# Flow_Pump.net
KiCad netlist of a schematic drawn in Altium Designer
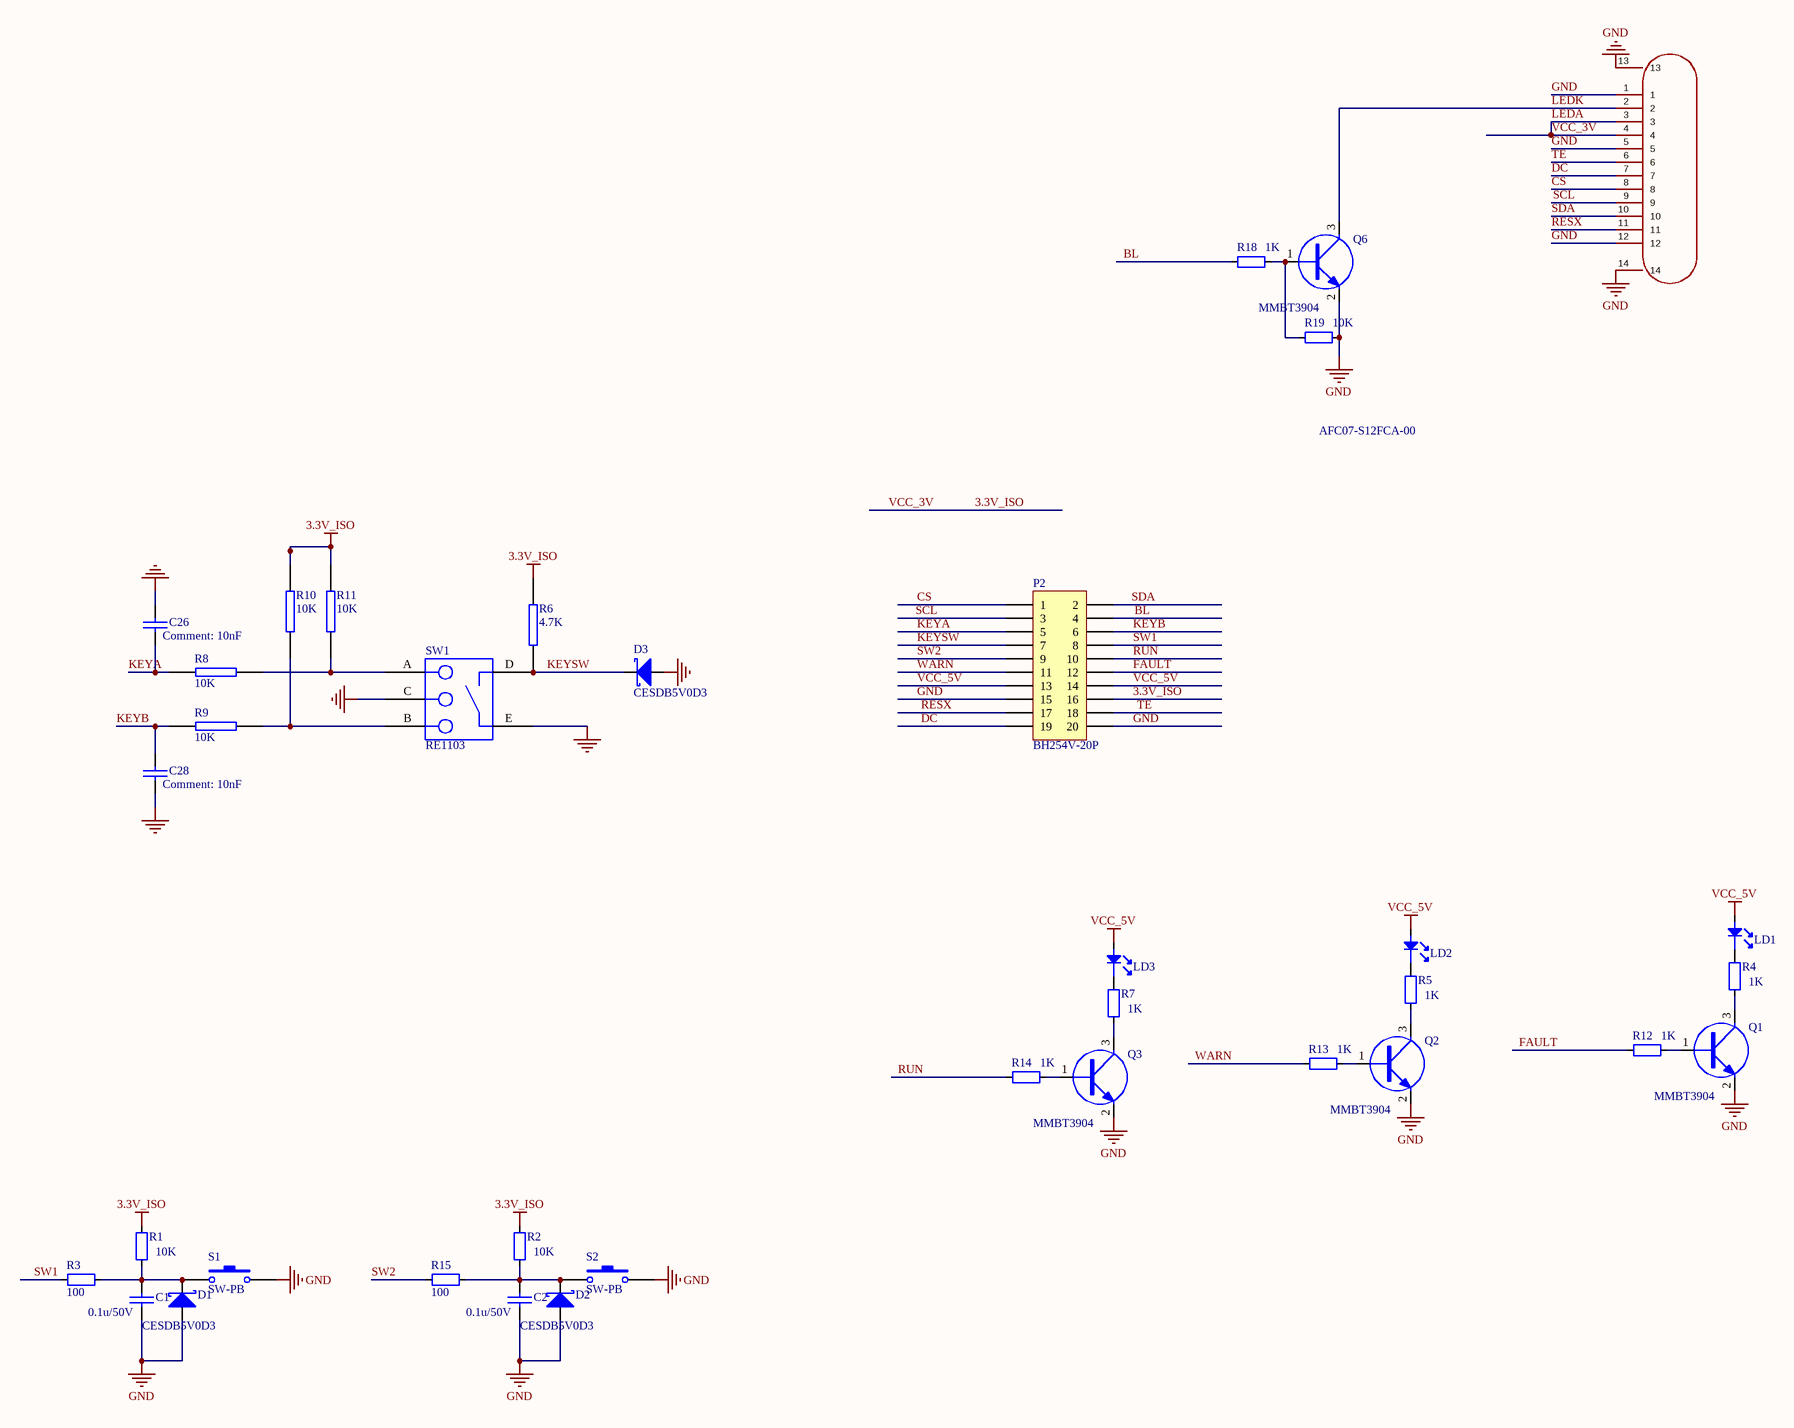
[diagram p0: Flow_Pump显示板.SchDoc]

(export (version "E")
  (design (tool "Eeschema 10.0.6"))
  (components
    (comp (ref "C1")
      (value "0.1u/50V")
      (footprint "0603C")
      (fields (field (name "Comment") "1uF/25V"))
      (libsource (lib "SM") (part "CAP"))
    )
    (comp (ref "C2")
      (value "0.1u/50V")
      (footprint "0603C")
      (fields (field (name "Comment") "1uF/25V"))
      (libsource (lib "SM") (part "CAP"))
    )
    (comp (ref "C26")
      (value "10nF")
      (footprint "0603C")
      (description "Capacitor")
      (libsource (lib "*") (part "CAP"))
    )
    (comp (ref "C28")
      (value "10nF")
      (footprint "0603C")
      (description "Capacitor")
      (libsource (lib "*") (part "CAP"))
    )
    (comp (ref "D1") (value "CESDB5V0D3") (footprint "SOD323") (libsource (lib "*") (part "DIODE S")))
    (comp (ref "D2") (value "CESDB5V0D3") (footprint "SOD323") (libsource (lib "*") (part "DIODE S")))
    (comp (ref "D3") (value "CESDB5V0D3") (footprint "SOD323") (libsource (lib "*") (part "DIODE S")))
    (comp (ref "FPC1")
      (value "AFC07-S12FCA-00")
      (footprint "FPC-SMD_12P-P0.50_AFC07-S12FCA-00")
      (libsource (lib "altium-import") (part "root_0_AFC07-S12FCA-00_"))
    )
    (comp (ref "LD1")
      (value "LED_Green_19-217")
      (footprint "0603led")
      (libsource (lib "RC_M_D_00") (part "LED_Green_19-217"))
    )
    (comp (ref "LD2")
      (value "LED_Green_19-217")
      (footprint "0603led")
      (libsource (lib "RC_M_D_00") (part "LED_Green_19-217"))
    )
    (comp (ref "LD3")
      (value "LED_Green_19-217")
      (footprint "0603led")
      (libsource (lib "RC_M_D_00") (part "LED_Green_19-217"))
    )
    (comp (ref "P2")
      (value "BH254V-20P")
      (footprint "DC-2.54-L-Z-20P")
      (description "Header, 10-Pin, Dual row")
      (fields (field (name "PUBLISHER") "Altium Limited"))
      (libsource (lib "Miscellaneous Connectors") (part "Header 10X2"))
    )
    (comp (ref "Q1")
      (value "MMBT3904")
      (footprint "SOT23-3")
      (libsource (lib "CenLib") (part "NPN_MMBT3904"))
    )
    (comp (ref "Q2")
      (value "MMBT3904")
      (footprint "SOT23-3")
      (libsource (lib "CenLib") (part "NPN_MMBT3904"))
    )
    (comp (ref "Q3")
      (value "MMBT3904")
      (footprint "SOT23-3")
      (libsource (lib "CenLib") (part "NPN_MMBT3904"))
    )
    (comp (ref "Q6")
      (value "MMBT3904")
      (footprint "SOT23-3")
      (libsource (lib "CenLib") (part "NPN_MMBT3904"))
    )
    (comp (ref "R1") (value "10K") (footprint "0603r") (libsource (lib "RC_M_D_00") (part "RES0603")))
    (comp (ref "R2") (value "10K") (footprint "0603r") (libsource (lib "RC_M_D_00") (part "RES0603")))
    (comp (ref "R3") (value "100") (footprint "0603r") (libsource (lib "RC_M_D_00") (part "RES0603")))
    (comp (ref "R4") (value "1K") (footprint "0603r") (libsource (lib "RC_M_D_00") (part "RES0603")))
    (comp (ref "R5") (value "1K") (footprint "0603r") (libsource (lib "RC_M_D_00") (part "RES0603")))
    (comp (ref "R6") (value "4.7K") (footprint "0603R") (libsource (lib "*") (part "RES2")))
    (comp (ref "R7") (value "1K") (footprint "0603r") (libsource (lib "RC_M_D_00") (part "RES0603")))
    (comp (ref "R8") (value "10K") (footprint "0603R") (libsource (lib "*") (part "RES2")))
    (comp (ref "R9") (value "10K") (footprint "0603R") (libsource (lib "*") (part "RES2")))
    (comp (ref "R10") (value "10K") (footprint "0603R") (libsource (lib "*") (part "RES2")))
    (comp (ref "R11") (value "10K") (footprint "0603R") (libsource (lib "*") (part "RES2")))
    (comp (ref "R12") (value "1K") (footprint "0603r") (libsource (lib "RC_M_D_00") (part "RES0603")))
    (comp (ref "R13") (value "1K") (footprint "0603r") (libsource (lib "RC_M_D_00") (part "RES0603")))
    (comp (ref "R14") (value "1K") (footprint "0603r") (libsource (lib "RC_M_D_00") (part "RES0603")))
    (comp (ref "R15") (value "100") (footprint "0603r") (libsource (lib "RC_M_D_00") (part "RES0603")))
    (comp (ref "R18") (value "1K") (footprint "0603r") (libsource (lib "RC_M_D_00") (part "RES0603")))
    (comp (ref "R19") (value "10K") (footprint "0603r") (libsource (lib "RC_M_D_00") (part "RES0603")))
    (comp (ref "S1")
      (value "SW-PB")
      (footprint "TSW SMD-6*6*8")
      (description "Switch")
      (fields (field (name "PUBLISHER") "Altium Limited"))
      (libsource (lib "Miscellaneous Devices") (part "SW-PB"))
    )
    (comp (ref "S2")
      (value "SW-PB")
      (footprint "TSW SMD-6*6*8")
      (description "Switch")
      (fields (field (name "PUBLISHER") "Altium Limited"))
      (libsource (lib "Miscellaneous Devices") (part "SW-PB"))
    )
    (comp (ref "SW1") (value "RE1103") (footprint "EX1103S-D2-10") (libsource (lib "*") (part "RE1103")))
  )
  (nets
    (net (code "1") (name "/BL") (class "Default")
      (node (ref "P2") (pin "4") (pinfunction "4_4") (pintype "passive"))
      (node (ref "R18") (pin "1") (pinfunction "1_1") (pintype "passive"))
    )
    (net (code "2") (name "/CS") (class "Default")
      (node (ref "FPC1") (pin "8") (pinfunction "8_8") (pintype "passive"))
      (node (ref "P2") (pin "1") (pinfunction "1_1") (pintype "passive"))
    )
    (net (code "3") (name "/DC") (class "Default")
      (node (ref "FPC1") (pin "7") (pinfunction "7_7") (pintype "passive"))
      (node (ref "P2") (pin "19") (pinfunction "19_19") (pintype "passive"))
    )
    (net (code "4") (name "/FAULT") (class "Default")
      (node (ref "P2") (pin "12") (pinfunction "12_12") (pintype "passive"))
      (node (ref "R12") (pin "1") (pinfunction "1_1") (pintype "passive"))
    )
    (net (code "5") (name "/KEYA") (class "Default")
      (node (ref "C26") (pin "2") (pinfunction "2_2") (pintype "passive"))
      (node (ref "P2") (pin "5") (pinfunction "5_5") (pintype "passive"))
      (node (ref "R8") (pin "1") (pinfunction "1_1") (pintype "passive"))
    )
    (net (code "6") (name "/KEYB") (class "Default")
      (node (ref "C28") (pin "1") (pinfunction "1_1") (pintype "passive"))
      (node (ref "P2") (pin "6") (pinfunction "6_6") (pintype "passive"))
      (node (ref "R9") (pin "1") (pinfunction "1_1") (pintype "passive"))
    )
    (net (code "7") (name "/KEYSW") (class "Default")
      (node (ref "D3") (pin "2") (pinfunction "K_2") (pintype "passive"))
      (node (ref "P2") (pin "7") (pinfunction "7_7") (pintype "passive"))
      (node (ref "R6") (pin "2") (pinfunction "2_2") (pintype "passive"))
      (node (ref "SW1") (pin "D") (pintype "passive"))
    )
    (net (code "8") (name "/LEDK") (class "Default")
      (node (ref "FPC1") (pin "2") (pinfunction "2_2") (pintype "passive"))
      (node (ref "Q6") (pin "3") (pinfunction "C_3") (pintype "passive"))
    )
    (net (code "9") (name "/RESX") (class "Default")
      (node (ref "FPC1") (pin "11") (pinfunction "11_11") (pintype "passive"))
      (node (ref "P2") (pin "17") (pinfunction "17_17") (pintype "passive"))
    )
    (net (code "10") (name "/RUN") (class "Default")
      (node (ref "P2") (pin "10") (pinfunction "10_10") (pintype "passive"))
      (node (ref "R14") (pin "1") (pinfunction "1_1") (pintype "passive"))
    )
    (net (code "11") (name "/SCL") (class "Default")
      (node (ref "FPC1") (pin "9") (pinfunction "9_9") (pintype "passive"))
      (node (ref "P2") (pin "3") (pinfunction "3_3") (pintype "passive"))
    )
    (net (code "12") (name "/SDA") (class "Default")
      (node (ref "FPC1") (pin "10") (pinfunction "10_10") (pintype "passive"))
      (node (ref "P2") (pin "2") (pinfunction "2_2") (pintype "passive"))
    )
    (net (code "13") (name "/SW1") (class "Default")
      (node (ref "P2") (pin "8") (pinfunction "8_8") (pintype "passive"))
      (node (ref "R3") (pin "1") (pinfunction "1_1") (pintype "passive"))
    )
    (net (code "14") (name "/SW2") (class "Default")
      (node (ref "P2") (pin "9") (pinfunction "9_9") (pintype "passive"))
      (node (ref "R15") (pin "1") (pinfunction "1_1") (pintype "passive"))
    )
    (net (code "15") (name "/TE") (class "Default")
      (node (ref "FPC1") (pin "6") (pinfunction "6_6") (pintype "passive"))
      (node (ref "P2") (pin "18") (pinfunction "18_18") (pintype "passive"))
    )
    (net (code "16") (name "/WARN") (class "Default")
      (node (ref "P2") (pin "11") (pinfunction "11_11") (pintype "passive"))
      (node (ref "R13") (pin "1") (pinfunction "1_1") (pintype "passive"))
    )
    (net (code "17") (name "3.3V_ISO") (class "Default")
      (node (ref "FPC1") (pin "3") (pinfunction "3_3") (pintype "passive"))
      (node (ref "FPC1") (pin "4") (pinfunction "4_4") (pintype "passive"))
      (node (ref "P2") (pin "16") (pinfunction "16_16") (pintype "passive"))
      (node (ref "R1") (pin "1") (pinfunction "1_1") (pintype "passive"))
      (node (ref "R10") (pin "2") (pinfunction "2_2") (pintype "passive"))
      (node (ref "R11") (pin "2") (pinfunction "2_2") (pintype "passive"))
      (node (ref "R2") (pin "1") (pinfunction "1_1") (pintype "passive"))
      (node (ref "R6") (pin "1") (pinfunction "1_1") (pintype "passive"))
    )
    (net (code "18") (name "GND") (class "Default")
      (node (ref "C1") (pin "1") (pinfunction "1_1") (pintype "passive"))
      (node (ref "C2") (pin "1") (pinfunction "1_1") (pintype "passive"))
      (node (ref "C26") (pin "1") (pinfunction "1_1") (pintype "passive"))
      (node (ref "C28") (pin "2") (pinfunction "2_2") (pintype "passive"))
      (node (ref "D1") (pin "1") (pinfunction "A_1") (pintype "passive"))
      (node (ref "D2") (pin "1") (pinfunction "A_1") (pintype "passive"))
      (node (ref "D3") (pin "1") (pinfunction "A_1") (pintype "passive"))
      (node (ref "FPC1") (pin "1") (pinfunction "1_1") (pintype "passive"))
      (node (ref "FPC1") (pin "12") (pinfunction "12_12") (pintype "passive"))
      (node (ref "FPC1") (pin "13") (pinfunction "13_13") (pintype "passive"))
      (node (ref "FPC1") (pin "14") (pinfunction "14_14") (pintype "passive"))
      (node (ref "FPC1") (pin "5") (pinfunction "5_5") (pintype "passive"))
      (node (ref "P2") (pin "15") (pinfunction "15_15") (pintype "passive"))
      (node (ref "P2") (pin "20") (pinfunction "20_20") (pintype "passive"))
      (node (ref "Q1") (pin "2") (pinfunction "E_2") (pintype "passive"))
      (node (ref "Q2") (pin "2") (pinfunction "E_2") (pintype "passive"))
      (node (ref "Q3") (pin "2") (pinfunction "E_2") (pintype "passive"))
      (node (ref "Q6") (pin "2") (pinfunction "E_2") (pintype "passive"))
      (node (ref "R19") (pin "2") (pinfunction "2_2") (pintype "passive"))
      (node (ref "S1") (pin "2") (pinfunction "2_2") (pintype "passive"))
      (node (ref "S2") (pin "2") (pinfunction "2_2") (pintype "passive"))
      (node (ref "SW1") (pin "C") (pintype "passive"))
      (node (ref "SW1") (pin "E") (pintype "passive"))
    )
    (net (code "19") (name "Net-(D1-K)") (class "Default")
      (node (ref "C1") (pin "2") (pinfunction "2_2") (pintype "passive"))
      (node (ref "D1") (pin "2") (pinfunction "K_2") (pintype "passive"))
      (node (ref "R1") (pin "2") (pinfunction "2_2") (pintype "passive"))
      (node (ref "R3") (pin "2") (pinfunction "2_2") (pintype "passive"))
      (node (ref "S1") (pin "1") (pinfunction "1_1") (pintype "passive"))
    )
    (net (code "20") (name "Net-(D2-K)") (class "Default")
      (node (ref "C2") (pin "2") (pinfunction "2_2") (pintype "passive"))
      (node (ref "D2") (pin "2") (pinfunction "K_2") (pintype "passive"))
      (node (ref "R15") (pin "2") (pinfunction "2_2") (pintype "passive"))
      (node (ref "R2") (pin "2") (pinfunction "2_2") (pintype "passive"))
      (node (ref "S2") (pin "1") (pinfunction "1_1") (pintype "passive"))
    )
    (net (code "21") (name "Net-(LD1-Pad2)") (class "Default")
      (node (ref "LD1") (pin "2") (pinfunction "2_2") (pintype "passive"))
      (node (ref "R4") (pin "1") (pinfunction "1_1") (pintype "passive"))
    )
    (net (code "22") (name "Net-(LD2-Pad2)") (class "Default")
      (node (ref "LD2") (pin "2") (pinfunction "2_2") (pintype "passive"))
      (node (ref "R5") (pin "1") (pinfunction "1_1") (pintype "passive"))
    )
    (net (code "23") (name "Net-(LD3-Pad2)") (class "Default")
      (node (ref "LD3") (pin "2") (pinfunction "2_2") (pintype "passive"))
      (node (ref "R7") (pin "1") (pinfunction "1_1") (pintype "passive"))
    )
    (net (code "24") (name "Net-(Q1-B)") (class "Default")
      (node (ref "Q1") (pin "1") (pinfunction "B_1") (pintype "passive"))
      (node (ref "R12") (pin "2") (pinfunction "2_2") (pintype "passive"))
    )
    (net (code "25") (name "Net-(Q1-C)") (class "Default")
      (node (ref "Q1") (pin "3") (pinfunction "C_3") (pintype "passive"))
      (node (ref "R4") (pin "2") (pinfunction "2_2") (pintype "passive"))
    )
    (net (code "26") (name "Net-(Q2-B)") (class "Default")
      (node (ref "Q2") (pin "1") (pinfunction "B_1") (pintype "passive"))
      (node (ref "R13") (pin "2") (pinfunction "2_2") (pintype "passive"))
    )
    (net (code "27") (name "Net-(Q2-C)") (class "Default")
      (node (ref "Q2") (pin "3") (pinfunction "C_3") (pintype "passive"))
      (node (ref "R5") (pin "2") (pinfunction "2_2") (pintype "passive"))
    )
    (net (code "28") (name "Net-(Q3-B)") (class "Default")
      (node (ref "Q3") (pin "1") (pinfunction "B_1") (pintype "passive"))
      (node (ref "R14") (pin "2") (pinfunction "2_2") (pintype "passive"))
    )
    (net (code "29") (name "Net-(Q3-C)") (class "Default")
      (node (ref "Q3") (pin "3") (pinfunction "C_3") (pintype "passive"))
      (node (ref "R7") (pin "2") (pinfunction "2_2") (pintype "passive"))
    )
    (net (code "30") (name "Net-(Q6-B)") (class "Default")
      (node (ref "Q6") (pin "1") (pinfunction "B_1") (pintype "passive"))
      (node (ref "R18") (pin "2") (pinfunction "2_2") (pintype "passive"))
      (node (ref "R19") (pin "1") (pinfunction "1_1") (pintype "passive"))
    )
    (net (code "31") (name "Net-(R10-Pad1)") (class "Default")
      (node (ref "R10") (pin "1") (pinfunction "1_1") (pintype "passive"))
      (node (ref "R9") (pin "2") (pinfunction "2_2") (pintype "passive"))
      (node (ref "SW1") (pin "B") (pintype "passive"))
    )
    (net (code "32") (name "Net-(R11-Pad1)") (class "Default")
      (node (ref "R11") (pin "1") (pinfunction "1_1") (pintype "passive"))
      (node (ref "R8") (pin "2") (pinfunction "2_2") (pintype "passive"))
      (node (ref "SW1") (pin "A") (pintype "passive"))
    )
    (net (code "33") (name "VCC_5V") (class "Default")
      (node (ref "LD1") (pin "1") (pinfunction "1_1") (pintype "passive"))
      (node (ref "LD2") (pin "1") (pinfunction "1_1") (pintype "passive"))
      (node (ref "LD3") (pin "1") (pinfunction "1_1") (pintype "passive"))
      (node (ref "P2") (pin "13") (pinfunction "13_13") (pintype "passive"))
      (node (ref "P2") (pin "14") (pinfunction "14_14") (pintype "passive"))
    )
  )
)
